# robotic_arm_arduino_uno_shield_ece196.net
KiCad netlist of a schematic drawn in EAGLE
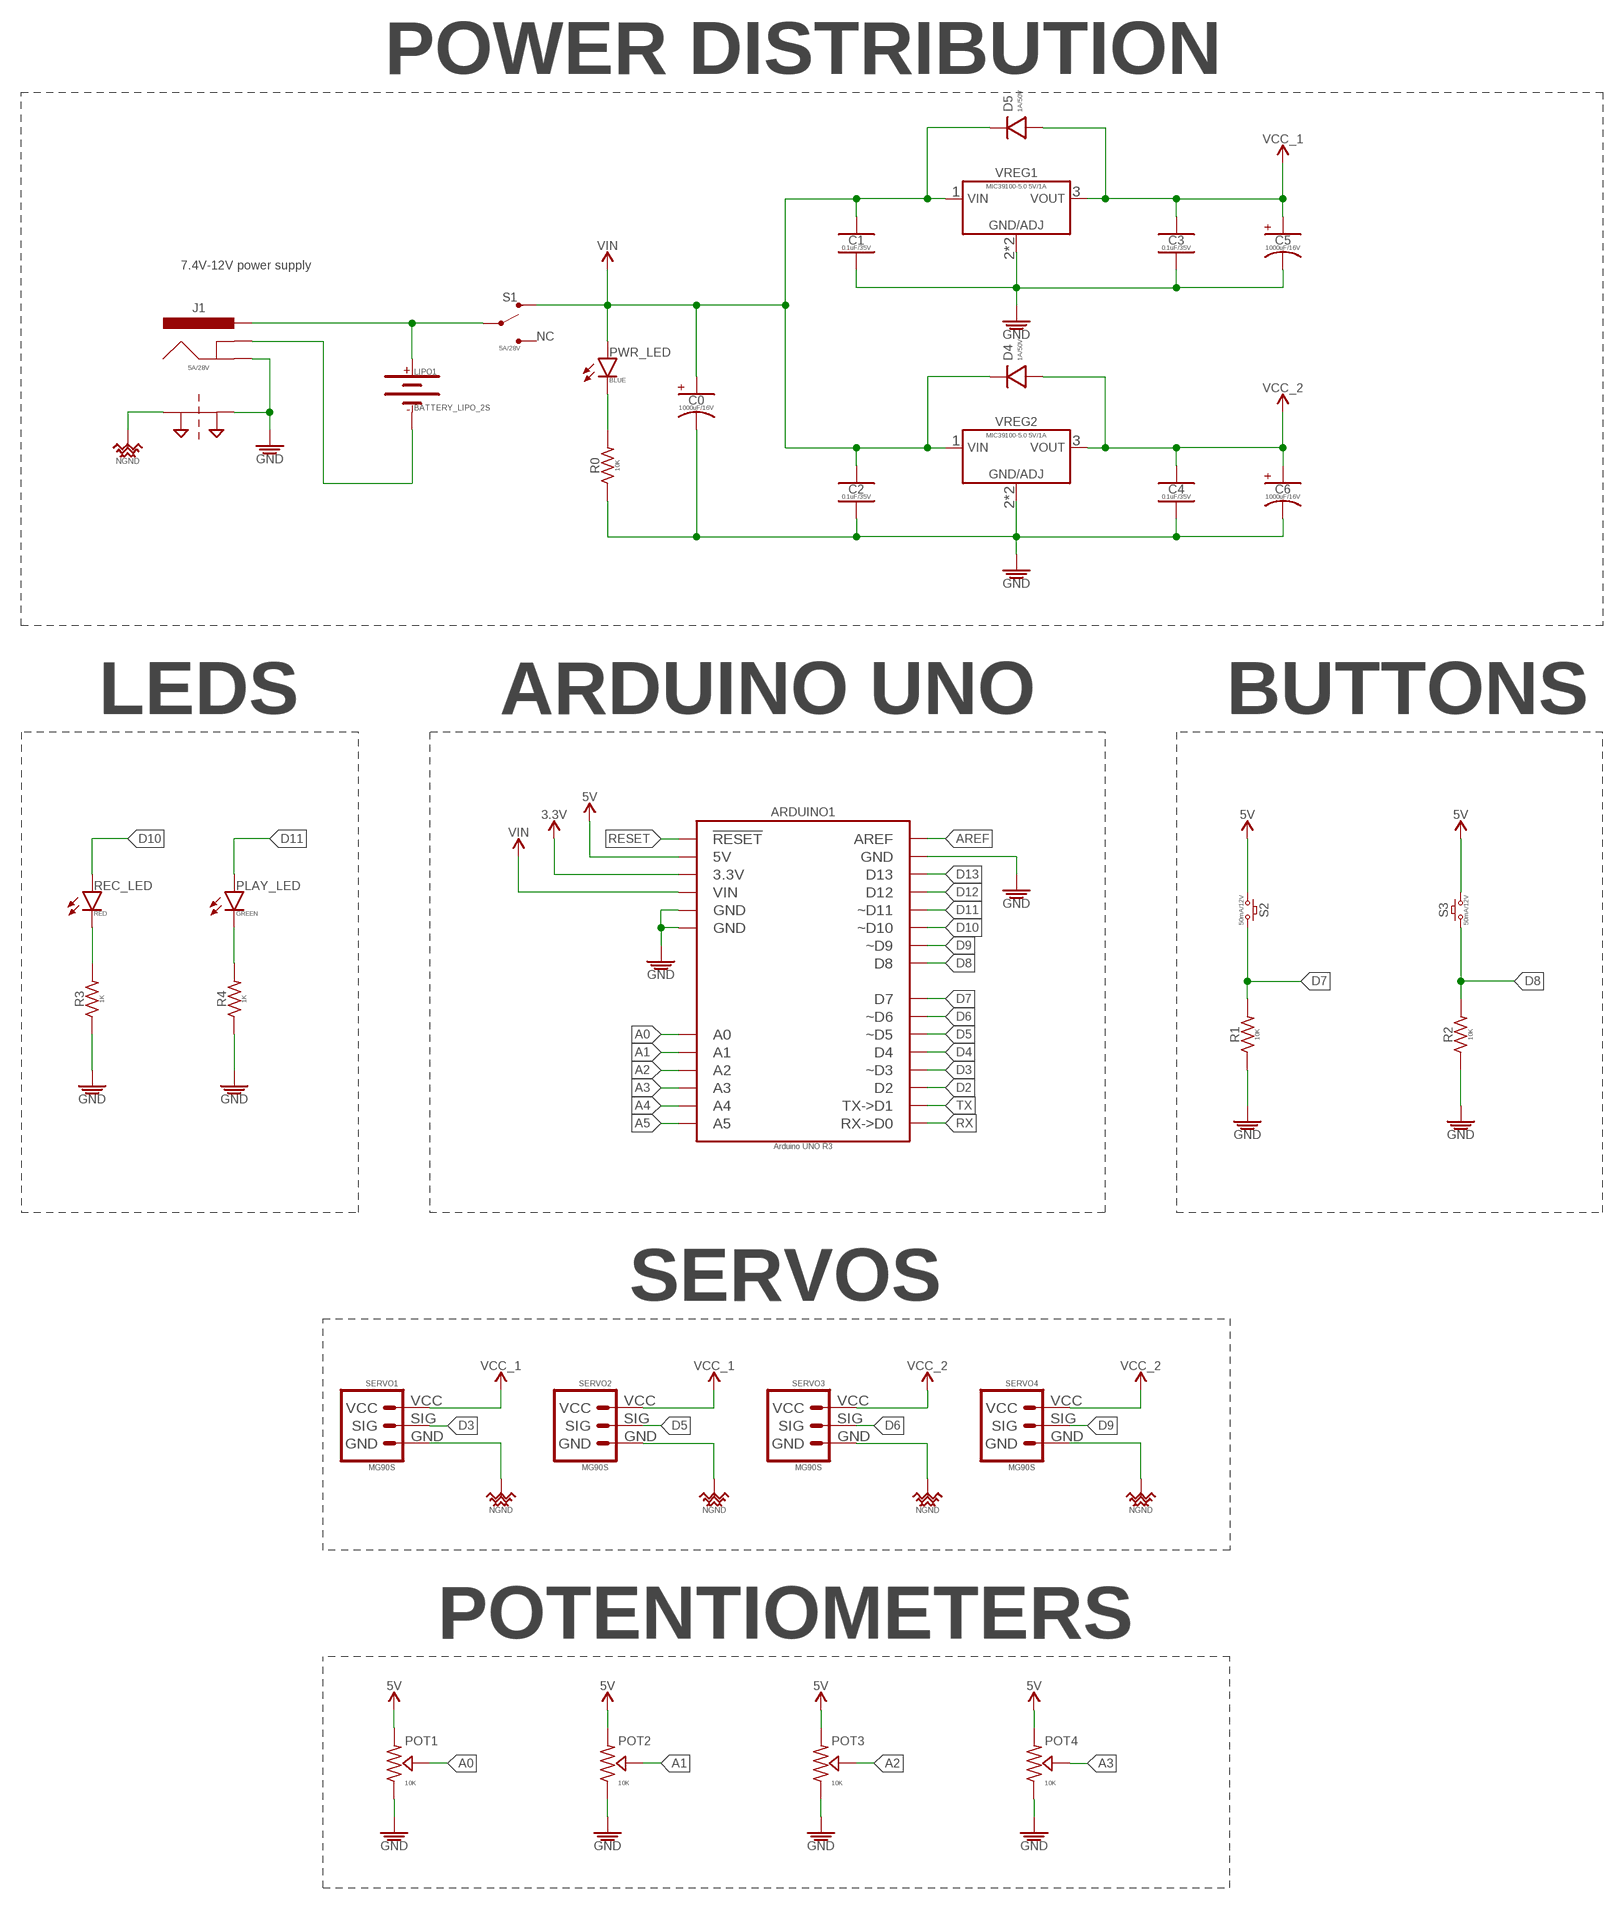
[diagram p0: schematic, sheet 1]

(export (version "E")
  (design (tool "Eeschema 10.0.6"))
  (components
    (comp (ref "ARDUINO1")
      (value "Arduino UNO R3")
      (footprint "eagle-import:ARDUINO_UNO_R3_NO-HOLES_NO-AVR-ISP_NO-I2C_NO-NC_NO-IOREF")
      (fields (field (name "MFR") "Arduino") (field (name "MPN") "A000066"))
      (libsource (lib "eagle-import") (part "ARDUINO_UNO_R3_NO-HOLES_NO-AVR-ISP_NO-I2C_NO-NC_NO-IOREF"))
    )
    (comp (ref "C0")
      (value "1000uF/16V")
      (footprint "eagle-import:_AE_PTH_DIA8-LS3.5-H21.50")
      (fields (field (name "MFR") "United Chemi-Con") (field (name "MPN") "EKZM160ELL102MH20D"))
      (libsource (lib "eagle-import") (part "1000UF-POLARIZED_PTH_16V-20%"))
    )
    (comp (ref "C1")
      (value "0.1uF/35V")
      (footprint "eagle-import:CAPC2012X95_SMD-0805")
      (fields (field (name "MFR") "Taiyo Yuden") (field (name "MPN") "GMK212BJ104KGHT"))
      (libsource (lib "eagle-import") (part "0.1UF_SMD-0805_35V-10%"))
    )
    (comp (ref "C2")
      (value "0.1uF/35V")
      (footprint "eagle-import:CAPC2012X95_SMD-0805")
      (fields (field (name "MFR") "Taiyo Yuden") (field (name "MPN") "GMK212BJ104KGHT"))
      (libsource (lib "eagle-import") (part "0.1UF_SMD-0805_35V-10%"))
    )
    (comp (ref "C3")
      (value "0.1uF/35V")
      (footprint "eagle-import:CAPC2012X95_SMD-0805")
      (fields (field (name "MFR") "Taiyo Yuden") (field (name "MPN") "GMK212BJ104KGHT"))
      (libsource (lib "eagle-import") (part "0.1UF_SMD-0805_35V-10%"))
    )
    (comp (ref "C4")
      (value "0.1uF/35V")
      (footprint "eagle-import:CAPC2012X95_SMD-0805")
      (fields (field (name "MFR") "Taiyo Yuden") (field (name "MPN") "GMK212BJ104KGHT"))
      (libsource (lib "eagle-import") (part "0.1UF_SMD-0805_35V-10%"))
    )
    (comp (ref "C5")
      (value "1000uF/16V")
      (footprint "eagle-import:_AE_PTH_DIA8-LS3.5-H21.50")
      (fields (field (name "MFR") "United Chemi-Con") (field (name "MPN") "EKZM160ELL102MH20D"))
      (libsource (lib "eagle-import") (part "1000UF-POLARIZED_PTH_16V-20%"))
    )
    (comp (ref "C6")
      (value "1000uF/16V")
      (footprint "eagle-import:_AE_PTH_DIA8-LS3.5-H21.50")
      (fields (field (name "MFR") "United Chemi-Con") (field (name "MPN") "EKZM160ELL102MH20D"))
      (libsource (lib "eagle-import") (part "1000UF-POLARIZED_PTH_16V-20%"))
    )
    (comp (ref "D4")
      (value "1A/50V")
      (footprint "eagle-import:SODFL3516X170")
      (fields (field (name "MFR") "Comchip Technology") (field (name "MPN") "CGRKM4001-HF"))
      (libsource (lib "eagle-import") (part "DIODE_GENERAL-PURPOSE_SMD_GP_1A-50V"))
    )
    (comp (ref "D5")
      (value "1A/50V")
      (footprint "eagle-import:SODFL3516X170")
      (fields (field (name "MFR") "Comchip Technology") (field (name "MPN") "CGRKM4001-HF"))
      (libsource (lib "eagle-import") (part "DIODE_GENERAL-PURPOSE_SMD_GP_1A-50V"))
    )
    (comp (ref "J1")
      (value "5A/28V")
      (footprint "eagle-import:POWER_JACK_PTH_ID2.1MM-OD5.5MM")
      (fields (field (name "MFR") "CUI Inc.") (field (name "MPN") "PJ-102A"))
      (libsource (lib "eagle-import") (part "POWER_JACK-BARREL_ID2.1MM-OD5.5MM_PTH_ID2.1MM-OD5.5MM"))
    )
    (comp (ref "LIPO1")
      (value "BATTERY_LIPO_2S")
      (footprint "eagle-import:DUAL_PTH_PADS")
      (libsource (lib "eagle-import") (part "BATTERY_LIPO_2S"))
    )
    (comp (ref "PLAY_LED")
      (value "GREEN")
      (footprint "eagle-import:LEDC2012X120_LED-0805")
      (fields (field (name "MFR") "Lite-On Inc.") (field (name "MPN") "LTST-C170KGKT"))
      (libsource (lib "eagle-import") (part "LED_SMD-0805_DISCRETE_GREEN"))
    )
    (comp (ref "POT1")
      (value "10K")
      (footprint "eagle-import:HDRVR3W64P254_1X3_812X254X850B")
      (fields (field (name "MFR") "TT Electronics/BI") (field (name "MPN") "P160KN2-0QA25B10K"))
      (libsource (lib "eagle-import") (part "POTENTIOMETER_CONNECTOR_PTH_VERT_FEMALE_2.54MM"))
    )
    (comp (ref "POT2")
      (value "10K")
      (footprint "eagle-import:HDRVR3W64P254_1X3_812X254X850B")
      (fields (field (name "MFR") "TT Electronics/BI") (field (name "MPN") "P160KN2-0QA25B10K"))
      (libsource (lib "eagle-import") (part "POTENTIOMETER_CONNECTOR_PTH_VERT_FEMALE_2.54MM"))
    )
    (comp (ref "POT3")
      (value "10K")
      (footprint "eagle-import:HDRVR3W64P254_1X3_812X254X850B")
      (fields (field (name "MFR") "TT Electronics/BI") (field (name "MPN") "P160KN2-0QA25B10K"))
      (libsource (lib "eagle-import") (part "POTENTIOMETER_CONNECTOR_PTH_VERT_FEMALE_2.54MM"))
    )
    (comp (ref "POT4")
      (value "10K")
      (footprint "eagle-import:HDRVR3W64P254_1X3_812X254X850B")
      (fields (field (name "MFR") "TT Electronics/BI") (field (name "MPN") "P160KN2-0QA25B10K"))
      (libsource (lib "eagle-import") (part "POTENTIOMETER_CONNECTOR_PTH_VERT_FEMALE_2.54MM"))
    )
    (comp (ref "PWR_LED")
      (value "BLUE")
      (footprint "eagle-import:LEDC2012X120_LED-0805")
      (fields (field (name "MFR") "Lite-On Inc.") (field (name "MPN") "LTST-C170TBKT"))
      (libsource (lib "eagle-import") (part "LED_SMD-0805_DISCRETE_BLUE"))
    )
    (comp (ref "R0")
      (value "10K")
      (footprint "eagle-import:RESC2012X60_SMD-0805")
      (fields (field (name "MFR") "Yageo") (field (name "MPN") "RC0805JR-0710KL"))
      (libsource (lib "eagle-import") (part "10KΩ_SMD-0805_1/8W-5%"))
    )
    (comp (ref "R1")
      (value "10K")
      (footprint "eagle-import:RESC2012X60_SMD-0805")
      (fields (field (name "MFR") "Yageo") (field (name "MPN") "RC0805JR-0710KL"))
      (libsource (lib "eagle-import") (part "10KΩ_SMD-0805_1/8W-5%"))
    )
    (comp (ref "R2")
      (value "10K")
      (footprint "eagle-import:RESC2012X60_SMD-0805")
      (fields (field (name "MFR") "Yageo") (field (name "MPN") "RC0805JR-0710KL"))
      (libsource (lib "eagle-import") (part "10KΩ_SMD-0805_1/8W-5%"))
    )
    (comp (ref "R3")
      (value "1K")
      (footprint "eagle-import:RESC2012X60_SMD-0805")
      (fields (field (name "MFR") "Yageo") (field (name "MPN") "RC0805JR-071KL"))
      (libsource (lib "eagle-import") (part "1KΩ_SMD-0805_1/8W-5%"))
    )
    (comp (ref "R4")
      (value "1K")
      (footprint "eagle-import:RESC2012X60_SMD-0805")
      (fields (field (name "MFR") "Yageo") (field (name "MPN") "RC0805JR-071KL"))
      (libsource (lib "eagle-import") (part "1KΩ_SMD-0805_1/8W-5%"))
    )
    (comp (ref "REC_LED")
      (value "RED")
      (footprint "eagle-import:LEDC2012X120_LED-0805")
      (fields (field (name "MFR") "Lite-On Inc.") (field (name "MPN") "LTST-C170KRKT"))
      (libsource (lib "eagle-import") (part "LED_SMD-0805_DISCRETE_RED"))
    )
    (comp (ref "S1")
      (value "5A/28V")
      (footprint "eagle-import:SW_TOGGLE_SPDT_5A-28V_13L-7W")
      (fields (field (name "MFR") "E-Switch") (field (name "MPN") "100SP1T1B4M2QE"))
      (libsource (lib "eagle-import") (part "SWITCH_SPDT_VERT_PTH_5A-28V_13L-7W_"))
    )
    (comp (ref "S2")
      (value "50mA/12V")
      (footprint "eagle-import:BTN_MOMENTARY_SPST-NO_PTH_L12-W12")
      (fields (field (name "MFR") "SparkFun Electronics") (field (name "MPN") "COM-10302"))
      (libsource (lib "eagle-import") (part "SWITCH_MOMENTARY_SPST_PTH_L12-W12-H7.2"))
    )
    (comp (ref "S3")
      (value "50mA/12V")
      (footprint "eagle-import:BTN_MOMENTARY_SPST-NO_PTH_L12-W12")
      (fields (field (name "MFR") "SparkFun Electronics") (field (name "MPN") "COM-10302"))
      (libsource (lib "eagle-import") (part "SWITCH_MOMENTARY_SPST_PTH_L12-W12-H7.2"))
    )
    (comp (ref "SERVO1")
      (value "MG90S")
      (footprint "eagle-import:HDRVR3W64P254_1X3_812X254X850B")
      (fields (field (name "MFR") "TowerPro"))
      (libsource (lib "eagle-import") (part "SERVO_MG90S_PTH_VERT_FEMALE_2.54MM"))
    )
    (comp (ref "SERVO2")
      (value "MG90S")
      (footprint "eagle-import:HDRVR3W64P254_1X3_812X254X850B")
      (fields (field (name "MFR") "TowerPro"))
      (libsource (lib "eagle-import") (part "SERVO_MG90S_PTH_VERT_FEMALE_2.54MM"))
    )
    (comp (ref "SERVO3")
      (value "MG90S")
      (footprint "eagle-import:HDRVR3W64P254_1X3_812X254X850B")
      (fields (field (name "MFR") "TowerPro"))
      (libsource (lib "eagle-import") (part "SERVO_MG90S_PTH_VERT_FEMALE_2.54MM"))
    )
    (comp (ref "SERVO4")
      (value "MG90S")
      (footprint "eagle-import:HDRVR3W64P254_1X3_812X254X850B")
      (fields (field (name "MFR") "TowerPro"))
      (libsource (lib "eagle-import") (part "SERVO_MG90S_PTH_VERT_FEMALE_2.54MM"))
    )
    (comp (ref "SUPPLY14")
      (value "NET_BRIDGE")
      (footprint "eagle-import:NET_BRIDGE")
      (libsource (lib "eagle-import") (part "NET_BRIDGE"))
    )
    (comp (ref "VREG1")
      (value "MIC39100-5.0 5V/1A")
      (footprint "eagle-import:SOT229P700X180-4")
      (fields (field (name "MFR") "Microchip Technology") (field (name "MPN") "MIC39100-5.0WS"))
      (libsource (lib "eagle-import") (part "MIC39100-XX_MIC39100-5.0_1A"))
    )
    (comp (ref "VREG2")
      (value "MIC39100-5.0 5V/1A")
      (footprint "eagle-import:SOT229P700X180-4")
      (fields (field (name "MFR") "Microchip Technology") (field (name "MPN") "MIC39100-5.0WS"))
      (libsource (lib "eagle-import") (part "MIC39100-XX_MIC39100-5.0_1A"))
    )
  )
  (nets
    (net (code "1") (name "3.3V") (class "Default")
      (node (ref "ARDUINO1") (pin "3.3V") (pinfunction "3.3V_3.3V") (pintype "bidirectional"))
    )
    (net (code "2") (name "5V") (class "Default")
      (node (ref "ARDUINO1") (pin "5V") (pinfunction "5V_5V") (pintype "bidirectional"))
      (node (ref "POT1") (pin "CCW") (pinfunction "CCW_CCW") (pintype "passive"))
      (node (ref "POT2") (pin "CCW") (pinfunction "CCW_CCW") (pintype "passive"))
      (node (ref "POT3") (pin "CCW") (pinfunction "CCW_CCW") (pintype "passive"))
      (node (ref "POT4") (pin "CCW") (pinfunction "CCW_CCW") (pintype "passive"))
      (node (ref "S2") (pin "1") (pinfunction "1_1") (pintype "passive"))
      (node (ref "S3") (pin "3") (pinfunction "2_3") (pintype "passive"))
    )
    (net (code "3") (name "A0") (class "Default")
      (node (ref "ARDUINO1") (pin "A0") (pinfunction "A0_A0") (pintype "bidirectional"))
      (node (ref "POT1") (pin "S") (pinfunction "S_S") (pintype "passive"))
    )
    (net (code "4") (name "A1") (class "Default")
      (node (ref "ARDUINO1") (pin "A1") (pinfunction "A1_A1") (pintype "bidirectional"))
      (node (ref "POT2") (pin "S") (pinfunction "S_S") (pintype "passive"))
    )
    (net (code "5") (name "A2") (class "Default")
      (node (ref "ARDUINO1") (pin "A2") (pinfunction "A2_A2") (pintype "bidirectional"))
      (node (ref "POT3") (pin "S") (pinfunction "S_S") (pintype "passive"))
    )
    (net (code "6") (name "A3") (class "Default")
      (node (ref "ARDUINO1") (pin "A3") (pinfunction "A3_A3") (pintype "bidirectional"))
      (node (ref "POT4") (pin "S") (pinfunction "S_S") (pintype "passive"))
    )
    (net (code "7") (name "A4") (class "Default")
      (node (ref "ARDUINO1") (pin "A4") (pinfunction "A4_A4") (pintype "bidirectional"))
    )
    (net (code "8") (name "A5") (class "Default")
      (node (ref "ARDUINO1") (pin "A5") (pinfunction "A5_A5") (pintype "bidirectional"))
    )
    (net (code "9") (name "AREF") (class "Default")
      (node (ref "ARDUINO1") (pin "AREF") (pinfunction "AREF_AREF") (pintype "bidirectional"))
    )
    (net (code "10") (name "D2") (class "Default")
      (node (ref "ARDUINO1") (pin "D2") (pinfunction "D2_D2") (pintype "bidirectional"))
    )
    (net (code "11") (name "D3") (class "Default")
      (node (ref "ARDUINO1") (pin "D3") (pinfunction "~{D3}_D3") (pintype "bidirectional"))
      (node (ref "SERVO1") (pin "SIG") (pinfunction "SIG_SIG") (pintype "passive"))
    )
    (net (code "12") (name "D4") (class "Default")
      (node (ref "ARDUINO1") (pin "D4") (pinfunction "D4_D4") (pintype "bidirectional"))
    )
    (net (code "13") (name "D5") (class "Default")
      (node (ref "ARDUINO1") (pin "D5") (pinfunction "~{D5}_D5") (pintype "bidirectional"))
      (node (ref "SERVO2") (pin "SIG") (pinfunction "SIG_SIG") (pintype "passive"))
    )
    (net (code "14") (name "D6") (class "Default")
      (node (ref "ARDUINO1") (pin "D6") (pinfunction "~{D6}_D6") (pintype "bidirectional"))
      (node (ref "SERVO3") (pin "SIG") (pinfunction "SIG_SIG") (pintype "passive"))
    )
    (net (code "15") (name "D7") (class "Default")
      (node (ref "ARDUINO1") (pin "D7") (pinfunction "D7_D7") (pintype "bidirectional"))
      (node (ref "R1") (pin "2") (pinfunction "2_2") (pintype "passive"))
      (node (ref "S2") (pin "3") (pinfunction "2_3") (pintype "passive"))
    )
    (net (code "16") (name "D8") (class "Default")
      (node (ref "ARDUINO1") (pin "D8") (pinfunction "D8_D8") (pintype "bidirectional"))
      (node (ref "R2") (pin "2") (pinfunction "2_2") (pintype "passive"))
      (node (ref "S3") (pin "1") (pinfunction "1_1") (pintype "passive"))
    )
    (net (code "17") (name "D9") (class "Default")
      (node (ref "ARDUINO1") (pin "D9") (pinfunction "~{D9}_D9") (pintype "bidirectional"))
      (node (ref "SERVO4") (pin "SIG") (pinfunction "SIG_SIG") (pintype "passive"))
    )
    (net (code "18") (name "D10") (class "Default")
      (node (ref "ARDUINO1") (pin "D10") (pinfunction "~{D10}_D10") (pintype "bidirectional"))
      (node (ref "REC_LED") (pin "A") (pinfunction "A_A") (pintype "passive"))
    )
    (net (code "19") (name "D11") (class "Default")
      (node (ref "ARDUINO1") (pin "D11") (pinfunction "~{D11}_D11") (pintype "bidirectional"))
      (node (ref "PLAY_LED") (pin "A") (pinfunction "A_A") (pintype "passive"))
    )
    (net (code "20") (name "D12") (class "Default")
      (node (ref "ARDUINO1") (pin "D12") (pinfunction "D12_D12") (pintype "bidirectional"))
    )
    (net (code "21") (name "D13") (class "Default")
      (node (ref "ARDUINO1") (pin "D13") (pinfunction "D13_D13") (pintype "bidirectional"))
    )
    (net (code "22") (name "GND") (class "Default")
      (node (ref "ARDUINO1") (pin "GND@1") (pinfunction "GND_GND@1") (pintype "bidirectional"))
      (node (ref "ARDUINO1") (pin "GND@2") (pinfunction "GND_GND@2") (pintype "bidirectional"))
      (node (ref "ARDUINO1") (pin "GND@3") (pinfunction "GND_GND@3") (pintype "bidirectional"))
      (node (ref "C0") (pin "-") (pinfunction "K_-") (pintype "passive"))
      (node (ref "C1") (pin "2") (pinfunction "2_2") (pintype "passive"))
      (node (ref "C2") (pin "2") (pinfunction "2_2") (pintype "passive"))
      (node (ref "C3") (pin "2") (pinfunction "2_2") (pintype "passive"))
      (node (ref "C4") (pin "2") (pinfunction "2_2") (pintype "passive"))
      (node (ref "C5") (pin "-") (pinfunction "K_-") (pintype "passive"))
      (node (ref "C6") (pin "-") (pinfunction "K_-") (pintype "passive"))
      (node (ref "J1") (pin "GND_JACK") (pinfunction "GND_JACK_GND_JACK") (pintype "bidirectional"))
      (node (ref "POT1") (pin "CW") (pinfunction "CW_CW") (pintype "passive"))
      (node (ref "POT2") (pin "CW") (pinfunction "CW_CW") (pintype "passive"))
      (node (ref "POT3") (pin "CW") (pinfunction "CW_CW") (pintype "passive"))
      (node (ref "POT4") (pin "CW") (pinfunction "CW_CW") (pintype "passive"))
      (node (ref "R0") (pin "1") (pinfunction "1_1") (pintype "passive"))
      (node (ref "R1") (pin "1") (pinfunction "1_1") (pintype "passive"))
      (node (ref "R2") (pin "1") (pinfunction "1_1") (pintype "passive"))
      (node (ref "R3") (pin "1") (pinfunction "1_1") (pintype "passive"))
      (node (ref "R4") (pin "1") (pinfunction "1_1") (pintype "passive"))
      (node (ref "SUPPLY14") (pin "P$2") (pinfunction "P$2_P$2") (pintype "passive"))
      (node (ref "VREG1") (pin "2") (pinfunction "GND_2") (pintype "power_in"))
      (node (ref "VREG1") (pin "TAB") (pinfunction "GND_TAB") (pintype "power_in"))
      (node (ref "VREG2") (pin "2") (pinfunction "GND_2") (pintype "power_in"))
      (node (ref "VREG2") (pin "TAB") (pinfunction "GND_TAB") (pintype "power_in"))
    )
    (net (code "23") (name "NGND") (class "Default")
      (node (ref "SERVO1") (pin "GND") (pinfunction "GND_GND") (pintype "passive"))
      (node (ref "SERVO2") (pin "GND") (pinfunction "GND_GND") (pintype "passive"))
      (node (ref "SERVO3") (pin "GND") (pinfunction "GND_GND") (pintype "passive"))
      (node (ref "SERVO4") (pin "GND") (pinfunction "GND_GND") (pintype "passive"))
      (node (ref "SUPPLY14") (pin "P$1") (pinfunction "P$1_P$1") (pintype "passive"))
    )
    (net (code "24") (name "Net-(LIPO1-P$1)") (class "Default")
      (node (ref "J1") (pin "PWR") (pinfunction "PWR_PWR") (pintype "bidirectional"))
      (node (ref "LIPO1") (pin "+") (pinfunction "P$1_+") (pintype "power_in"))
      (node (ref "S1") (pin "P") (pinfunction "P_P") (pintype "passive"))
    )
    (net (code "25") (name "Net-(LIPO1-P$2)") (class "Default")
      (node (ref "J1") (pin "GND_BATTERY") (pinfunction "GND_BATTERY_GND_BATTERY") (pintype "bidirectional"))
      (node (ref "LIPO1") (pin "-") (pinfunction "P$2_-") (pintype "power_in"))
    )
    (net (code "26") (name "Net-(PLAY_LED-PadK)") (class "Default")
      (node (ref "PLAY_LED") (pin "K") (pinfunction "K_K") (pintype "passive"))
      (node (ref "R4") (pin "2") (pinfunction "2_2") (pintype "passive"))
    )
    (net (code "27") (name "Net-(PWR_LED-PadK)") (class "Default")
      (node (ref "PWR_LED") (pin "K") (pinfunction "K_K") (pintype "passive"))
      (node (ref "R0") (pin "2") (pinfunction "2_2") (pintype "passive"))
    )
    (net (code "28") (name "Net-(R3-Pad2)") (class "Default")
      (node (ref "R3") (pin "2") (pinfunction "2_2") (pintype "passive"))
      (node (ref "REC_LED") (pin "K") (pinfunction "K_K") (pintype "passive"))
    )
    (net (code "29") (name "RESET") (class "Default")
      (node (ref "ARDUINO1") (pin "RESET@1") (pinfunction "~{RESET}_RESET@1") (pintype "bidirectional"))
    )
    (net (code "30") (name "RX") (class "Default")
      (node (ref "ARDUINO1") (pin "D0") (pinfunction "RX->D0_D0") (pintype "bidirectional"))
    )
    (net (code "31") (name "TX") (class "Default")
      (node (ref "ARDUINO1") (pin "D1") (pinfunction "TX->D1_D1") (pintype "bidirectional"))
    )
    (net (code "32") (name "VCC_1") (class "Default")
      (node (ref "C3") (pin "1") (pinfunction "1_1") (pintype "passive"))
      (node (ref "C5") (pin "+") (pinfunction "A_+") (pintype "passive"))
      (node (ref "D5") (pin "A") (pinfunction "A_A") (pintype "passive"))
      (node (ref "SERVO1") (pin "VCC") (pinfunction "VCC_VCC") (pintype "passive"))
      (node (ref "SERVO2") (pin "VCC") (pinfunction "VCC_VCC") (pintype "passive"))
      (node (ref "VREG1") (pin "3") (pinfunction "VO_3") (pintype "power_in"))
    )
    (net (code "33") (name "VCC_2") (class "Default")
      (node (ref "C4") (pin "1") (pinfunction "1_1") (pintype "passive"))
      (node (ref "C6") (pin "+") (pinfunction "A_+") (pintype "passive"))
      (node (ref "D4") (pin "A") (pinfunction "A_A") (pintype "passive"))
      (node (ref "SERVO3") (pin "VCC") (pinfunction "VCC_VCC") (pintype "passive"))
      (node (ref "SERVO4") (pin "VCC") (pinfunction "VCC_VCC") (pintype "passive"))
      (node (ref "VREG2") (pin "3") (pinfunction "VO_3") (pintype "power_in"))
    )
    (net (code "34") (name "VIN") (class "Default")
      (node (ref "ARDUINO1") (pin "VIN") (pinfunction "VIN_VIN") (pintype "bidirectional"))
      (node (ref "C0") (pin "+") (pinfunction "A_+") (pintype "passive"))
      (node (ref "C1") (pin "1") (pinfunction "1_1") (pintype "passive"))
      (node (ref "C2") (pin "1") (pinfunction "1_1") (pintype "passive"))
      (node (ref "D4") (pin "K") (pinfunction "K_K") (pintype "passive"))
      (node (ref "D5") (pin "K") (pinfunction "K_K") (pintype "passive"))
      (node (ref "PWR_LED") (pin "A") (pinfunction "A_A") (pintype "passive"))
      (node (ref "S1") (pin "S1") (pinfunction "S1_S1") (pintype "passive"))
      (node (ref "VREG1") (pin "1") (pinfunction "VI_1") (pintype "power_in"))
      (node (ref "VREG2") (pin "1") (pinfunction "VI_1") (pintype "power_in"))
    )
    (net (code "35") (name "unconnected-(S1-PadS2)") (class "Default")
      (node (ref "S1") (pin "S2") (pinfunction "S2_S2") (pintype "passive"))
    )
  )
)
